# Main.net
KiCad netlist of a schematic drawn in Altium Designer
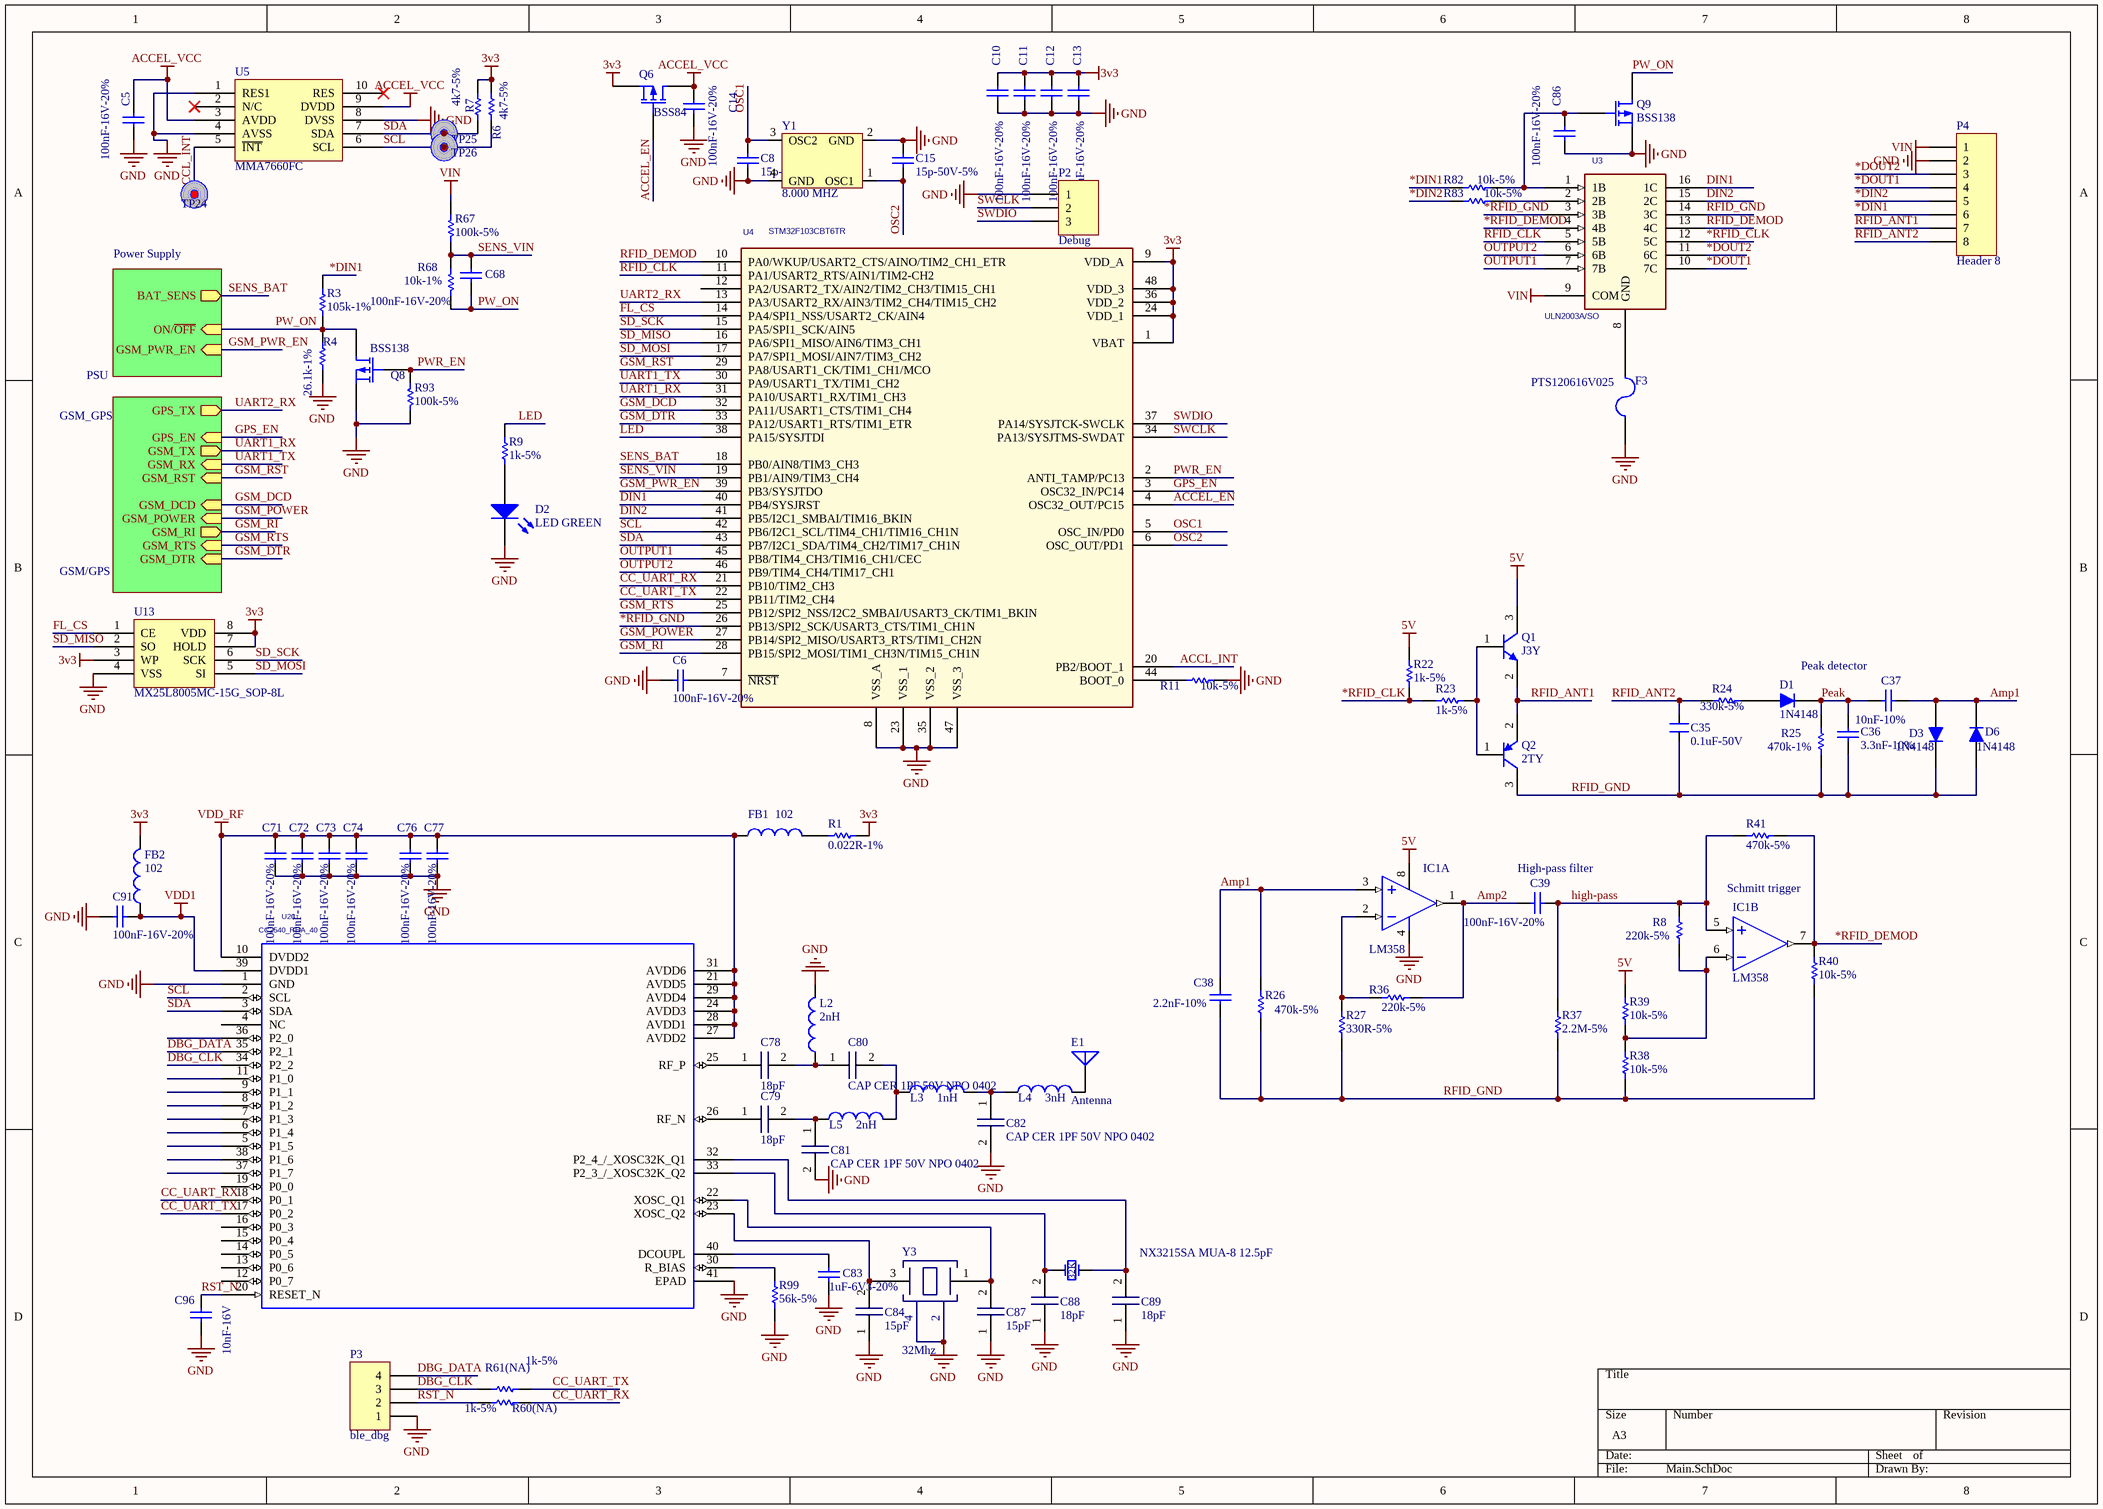
[diagram p0: Main.SchDoc]

(export (version "E")
  (design (tool "Eeschema 10.0.6"))
  (components
    (comp (ref "C5")
      (value "100nF-16V-20%")
      (footprint "C0402")
      (description "CAP CER 0.1UF 16V Y5V 0402")
      (fields
        (field (name "MANUFACTURER") "Yageo")
        (field (name "DIGI-KEY PART NUMBER") "311-1047-1-ND")
        (field (name "PUBLISHER") "Altium Limited")
      )
      (libsource (lib "Miscellaneous Devices") (part "Cap"))
    )
    (comp (ref "C6")
      (value "100nF-16V-20%")
      (footprint "C0402")
      (description "CAP CER 0.1UF 16V Y5V 0402")
      (fields
        (field (name "MANUFACTURER") "Yageo")
        (field (name "DIGI-KEY PART NUMBER") "311-1047-1-ND")
        (field (name "PUBLISHER") "Altium Limited")
      )
      (libsource (lib "Miscellaneous Devices") (part "Cap"))
    )
    (comp (ref "C8")
      (value "15p-50V-5%")
      (footprint "C0402")
      (description "CAP CER 15PF 50V 5% NPO 0402")
      (fields
        (field (name "MANUFACTURER") "Yageo")
        (field (name "DIGI-KEY PART NUMBER") "311-1017-1-ND")
        (field (name "PUBLISHER") "Altium Limited")
      )
      (libsource (lib "Miscellaneous Devices") (part "Cap"))
    )
    (comp (ref "C10")
      (value "100nF-16V-20%")
      (footprint "C0402")
      (description "CAP CER 0.1UF 16V Y5V 0402")
      (fields
        (field (name "MANUFACTURER") "Yageo")
        (field (name "DIGI-KEY PART NUMBER") "311-1047-1-ND")
        (field (name "PUBLISHER") "Altium Limited")
      )
      (libsource (lib "Miscellaneous Devices") (part "Cap"))
    )
    (comp (ref "C11")
      (value "100nF-16V-20%")
      (footprint "C0402")
      (description "CAP CER 0.1UF 16V Y5V 0402")
      (fields
        (field (name "MANUFACTURER") "Yageo")
        (field (name "DIGI-KEY PART NUMBER") "311-1047-1-ND")
        (field (name "PUBLISHER") "Altium Limited")
      )
      (libsource (lib "Miscellaneous Devices") (part "Cap"))
    )
    (comp (ref "C12")
      (value "100nF-16V-20%")
      (footprint "C0402")
      (description "CAP CER 0.1UF 16V Y5V 0402")
      (fields
        (field (name "MANUFACTURER") "Yageo")
        (field (name "DIGI-KEY PART NUMBER") "311-1047-1-ND")
        (field (name "PUBLISHER") "Altium Limited")
      )
      (libsource (lib "Miscellaneous Devices") (part "Cap"))
    )
    (comp (ref "C13")
      (value "100nF-16V-20%")
      (footprint "C0402")
      (description "CAP CER 0.1UF 16V Y5V 0402")
      (fields
        (field (name "MANUFACTURER") "Yageo")
        (field (name "DIGI-KEY PART NUMBER") "311-1047-1-ND")
        (field (name "PUBLISHER") "Altium Limited")
      )
      (libsource (lib "Miscellaneous Devices") (part "Cap"))
    )
    (comp (ref "C14")
      (value "100nF-16V-20%")
      (footprint "C0402")
      (description "CAP CER 0.1UF 16V Y5V 0402")
      (fields
        (field (name "MANUFACTURER") "Yageo")
        (field (name "DIGI-KEY PART NUMBER") "311-1047-1-ND")
        (field (name "PUBLISHER") "Altium Limited")
      )
      (libsource (lib "Miscellaneous Devices") (part "Cap"))
    )
    (comp (ref "C15")
      (value "15p-50V-5%")
      (footprint "C0402")
      (description "CAP CER 15PF 50V 5% NPO 0402")
      (fields
        (field (name "MANUFACTURER") "Yageo")
        (field (name "DIGI-KEY PART NUMBER") "311-1017-1-ND")
        (field (name "PUBLISHER") "Altium Limited")
      )
      (libsource (lib "Miscellaneous Devices") (part "Cap"))
    )
    (comp (ref "C35")
      (value "0.1uF-50V")
      (footprint "C0603")
      (description "CAP CER 0.1UF 50V Y5V 0603")
      (fields (field (name "DIGI-KEY PART NUMBER") "311-1343-2-ND") (field (name "MANUFACTURER") "Yageo"))
      (libsource (lib "syhaunguyen") (part "CN2"))
    )
    (comp (ref "C36")
      (value "3.3nF-10%")
      (footprint "C0402")
      (description "CAP CER 3300PF 50V 10% X7R 0402")
      (fields (field (name "DIGI-KEY PART NUMBER") "311-1034-2-ND") (field (name "MANUFACTURER") "Yageo"))
      (libsource (lib "Capacitor") (part "1nF-50V-C0805"))
    )
    (comp (ref "C37")
      (value "10nF-10%")
      (footprint "C0402")
      (description "Non-Polarized Capacitor")
      (fields (field (name "DIGI-KEY PART NUMBER") "CC0402KRX7R9BB103") (field (name "MANUFACTURER") "Yageo"))
      (libsource (lib "Capacitor") (part "10nF-50V-C0805"))
    )
    (comp (ref "C38")
      (value "2.2nF-10%")
      (footprint "C0402")
      (description "CAP CER 2200PF 50V 10% X7R 0402")
      (fields (field (name "DIGI-KEY PART NUMBER") "311-1037-2-ND") (field (name "MANUFACTURER") "Yageo"))
      (libsource (lib "Capacitor") (part "2.2nF-50V-C0805"))
    )
    (comp (ref "C39")
      (value "100nF-16V-20%")
      (footprint "C0402")
      (description "CAP CER 0.1UF 16V Y5V 0402")
      (fields
        (field (name "MANUFACTURER") "Yageo")
        (field (name "DIGI-KEY PART NUMBER") "311-1047-1-ND")
        (field (name "PUBLISHER") "Altium Limited")
      )
      (libsource (lib "Miscellaneous Devices") (part "Cap"))
    )
    (comp (ref "C68")
      (value "100nF-16V-20%")
      (footprint "C0402")
      (description "CAP CER 0.1UF 16V Y5V 0402")
      (fields
        (field (name "MANUFACTURER") "Yageo")
        (field (name "DIGI-KEY PART NUMBER") "311-1047-1-ND")
        (field (name "PUBLISHER") "Altium Limited")
      )
      (libsource (lib "Miscellaneous Devices") (part "Cap"))
    )
    (comp (ref "C71")
      (value "100nF-16V-20%")
      (footprint "C0402")
      (description "CAP CER 0.1UF 16V Y5V 0402")
      (fields
        (field (name "MANUFACTURER") "Yageo")
        (field (name "DIGI-KEY PART NUMBER") "311-1047-1-ND")
        (field (name "PUBLISHER") "Altium Limited")
      )
      (libsource (lib "Miscellaneous Devices") (part "Cap"))
    )
    (comp (ref "C72")
      (value "100nF-16V-20%")
      (footprint "C0402")
      (description "CAP CER 0.1UF 16V Y5V 0402")
      (fields
        (field (name "MANUFACTURER") "Yageo")
        (field (name "DIGI-KEY PART NUMBER") "311-1047-1-ND")
        (field (name "PUBLISHER") "Altium Limited")
      )
      (libsource (lib "Miscellaneous Devices") (part "Cap"))
    )
    (comp (ref "C73")
      (value "100nF-16V-20%")
      (footprint "C0402")
      (description "CAP CER 0.1UF 16V Y5V 0402")
      (fields
        (field (name "MANUFACTURER") "Yageo")
        (field (name "DIGI-KEY PART NUMBER") "311-1047-1-ND")
        (field (name "PUBLISHER") "Altium Limited")
      )
      (libsource (lib "Miscellaneous Devices") (part "Cap"))
    )
    (comp (ref "C74")
      (value "100nF-16V-20%")
      (footprint "C0402")
      (description "CAP CER 0.1UF 16V Y5V 0402")
      (fields
        (field (name "MANUFACTURER") "Yageo")
        (field (name "DIGI-KEY PART NUMBER") "311-1047-1-ND")
        (field (name "PUBLISHER") "Altium Limited")
      )
      (libsource (lib "Miscellaneous Devices") (part "Cap"))
    )
    (comp (ref "C76")
      (value "100nF-16V-20%")
      (footprint "C0402")
      (description "CAP CER 0.1UF 16V Y5V 0402")
      (fields
        (field (name "MANUFACTURER") "Yageo")
        (field (name "DIGI-KEY PART NUMBER") "311-1047-1-ND")
        (field (name "PUBLISHER") "Altium Limited")
      )
      (libsource (lib "Miscellaneous Devices") (part "Cap"))
    )
    (comp (ref "C77")
      (value "100nF-16V-20%")
      (footprint "C0402")
      (description "CAP CER 0.1UF 16V Y5V 0402")
      (fields
        (field (name "MANUFACTURER") "Yageo")
        (field (name "DIGI-KEY PART NUMBER") "311-1047-1-ND")
        (field (name "PUBLISHER") "Altium Limited")
      )
      (libsource (lib "Miscellaneous Devices") (part "Cap"))
    )
    (comp (ref "C78")
      (value "18pF")
      (footprint "C0402")
      (fields
        (field (name "MANUFACTURER") "Yageo")
        (field (name "DIGI-KEY PART NUMBER") "311-1018-1-ND")
        (field (name "MANUFACTURER PART NUMBER") "CC0402JRNPO9BN220")
      )
      (libsource (lib "Capacitor") (part "18pF"))
    )
    (comp (ref "C79")
      (value "18pF")
      (footprint "C0402")
      (fields
        (field (name "MANUFACTURER") "Yageo")
        (field (name "DIGI-KEY PART NUMBER") "311-1018-1-ND")
        (field (name "MANUFACTURER PART NUMBER") "CC0402JRNPO9BN220")
      )
      (libsource (lib "Capacitor") (part "18pF"))
    )
    (comp (ref "C80")
      (value "CAP CER 1PF 50V NPO 0402")
      (footprint "C0402")
      (fields
        (field (name "DIGI-KEY PART NUMBER") "CC0402CRNPO9BN1R0-ND")
        (field (name "MANUFACTURER") "Yageo")
        (field (name "MANUFACTURER PART NUMBER") "CC0402CRNPO9BN1R0")
      )
      (libsource (lib "Capacitor") (part "1pF"))
    )
    (comp (ref "C81")
      (value "CAP CER 1PF 50V NPO 0402")
      (footprint "C0402")
      (fields
        (field (name "DIGI-KEY PART NUMBER") "CC0402CRNPO9BN1R0-ND")
        (field (name "MANUFACTURER") "Yageo")
        (field (name "MANUFACTURER PART NUMBER") "CC0402CRNPO9BN1R0")
      )
      (libsource (lib "Capacitor") (part "1pF"))
    )
    (comp (ref "C82")
      (value "CAP CER 1PF 50V NPO 0402")
      (footprint "C0402")
      (fields
        (field (name "DIGI-KEY PART NUMBER") "CC0402CRNPO9BN1R0-ND")
        (field (name "MANUFACTURER") "Yageo")
        (field (name "MANUFACTURER PART NUMBER") "CC0402CRNPO9BN1R0")
      )
      (libsource (lib "Capacitor") (part "1pF"))
    )
    (comp (ref "C83")
      (value "1uF-6V3-20%")
      (footprint "C0402")
      (description "CAP CER 1UF 6.3V Y5V 0402")
      (fields
        (field (name "MANUFACTURER") "Yageo")
        (field (name "DIGI-KEY PART NUMBER") "311-1377-2-ND")
        (field (name "PUBLISHER") "Altium Limited")
      )
      (libsource (lib "Miscellaneous Devices") (part "Cap"))
    )
    (comp (ref "C84")
      (value "15pF")
      (footprint "C0402")
      (fields
        (field (name "MANUFACTURER") "Yageo")
        (field (name "DIGI-KEY PART NUMBER") "311-1018-1-ND")
        (field (name "MANUFACTURER PART NUMBER") "CC0402JRNPO9BN220")
      )
      (libsource (lib "Capacitor") (part "15pF"))
    )
    (comp (ref "C86")
      (value "100nF-16V-20%")
      (footprint "C0402")
      (description "CAP CER 0.1UF 16V Y5V 0402")
      (fields
        (field (name "MANUFACTURER") "Yageo")
        (field (name "DIGI-KEY PART NUMBER") "311-1047-1-ND")
        (field (name "PUBLISHER") "Altium Limited")
      )
      (libsource (lib "Miscellaneous Devices") (part "Cap"))
    )
    (comp (ref "C87")
      (value "15pF")
      (footprint "C0402")
      (fields
        (field (name "MANUFACTURER") "Yageo")
        (field (name "DIGI-KEY PART NUMBER") "311-1018-1-ND")
        (field (name "MANUFACTURER PART NUMBER") "CC0402JRNPO9BN220")
      )
      (libsource (lib "Capacitor") (part "15pF"))
    )
    (comp (ref "C88")
      (value "18pF")
      (footprint "C0402")
      (fields
        (field (name "MANUFACTURER") "Yageo")
        (field (name "DIGI-KEY PART NUMBER") "311-1018-1-ND")
        (field (name "MANUFACTURER PART NUMBER") "CC0402JRNPO9BN220")
      )
      (libsource (lib "Capacitor") (part "18pF"))
    )
    (comp (ref "C89")
      (value "18pF")
      (footprint "C0402")
      (fields
        (field (name "MANUFACTURER") "Yageo")
        (field (name "DIGI-KEY PART NUMBER") "311-1018-1-ND")
        (field (name "MANUFACTURER PART NUMBER") "CC0402JRNPO9BN220")
      )
      (libsource (lib "Capacitor") (part "18pF"))
    )
    (comp (ref "C91")
      (value "100nF-16V-20%")
      (footprint "C0402")
      (description "CAP CER 0.1UF 16V Y5V 0402")
      (fields
        (field (name "MANUFACTURER") "Yageo")
        (field (name "DIGI-KEY PART NUMBER") "311-1047-1-ND")
        (field (name "PUBLISHER") "Altium Limited")
      )
      (libsource (lib "Miscellaneous Devices") (part "Cap"))
    )
    (comp (ref "C96")
      (value "10nF-16V")
      (footprint "C0402")
      (description "CAP CER 10000PF 16V 10% X7R 0402")
      (fields (field (name "DIGI-KEY PART NUMBER") "311-1042-2-ND") (field (name "MANUFACTURER") "Yageo"))
      (libsource (lib "Capacitor_0402") (part "10nF-16V-C0402-10%"))
    )
    (comp (ref "D1")
      (value "1N4148")
      (footprint "DO-213AA")
      (description "DIODE SMALL SIG 100V 0.2A ALF2")
      (fields
        (field (name "DIGI-KEY PART NUMBER") "568-1360-1-ND")
        (field (name "MANUFACTURER") "NXP Semiconductors")
      )
      (libsource (lib "Active Components") (part "1N4148"))
    )
    (comp (ref "D2")
      (value "LED GREEN")
      (footprint "LED0603-G")
      (description "LED GREEN CLEAR THIN 0603 SMD")
      (fields
        (field (name "DIGI-KEY PART NUMBER") "160-1446-2-ND")
        (field (name "MANUFACTURER") "Lite-On Inc")
        (field (name "PUBLISHER") "Altium Limited")
      )
      (libsource (lib "Miscellaneous Devices") (part "LED2"))
    )
    (comp (ref "D3")
      (value "1N4148")
      (footprint "DO-213AA")
      (description "DIODE SMALL SIG 100V 0.2A ALF2")
      (fields
        (field (name "DIGI-KEY PART NUMBER") "568-1360-1-ND")
        (field (name "MANUFACTURER") "NXP Semiconductors")
      )
      (libsource (lib "Active Components") (part "1N4148"))
    )
    (comp (ref "D6")
      (value "1N4148")
      (footprint "DO-213AA")
      (description "DIODE SMALL SIG 100V 0.2A ALF2")
      (fields
        (field (name "DIGI-KEY PART NUMBER") "568-1360-1-ND")
        (field (name "MANUFACTURER") "NXP Semiconductors")
      )
      (libsource (lib "Active Components") (part "1N4148"))
    )
    (comp (ref "E1")
      (value "Antenna")
      (footprint "A10192-ANTENOVA")
      (description "Generic Antenna")
      (fields (field (name "PUBLISHER") "Altium Limited"))
      (libsource (lib "Miscellaneous Devices") (part "Antenna"))
    )
    (comp (ref "F3")
      (value "PTS120616V025")
      (footprint "PTC1206")
      (description "PTC RESETTABLE SMD 1206 16V .25A")
      (fields
        (field (name "DIGI-KEY PART NUMBER") "283-3137-2-ND")
        (field (name "MANUFACTURER") "Cooper Bussmann")
        (field (name "PUBLISHER") "Altium Limited")
      )
      (libsource (lib "Miscellaneous Devices") (part "Fuse 2"))
    )
    (comp (ref "FB1")
      (value "102")
      (footprint "R0402")
      (description "Inductor")
      (fields
        (field (name "DIGI-KEY PART NUMBER") "490-1174-1-ND")
        (field (name "MANUFACTURER PART NUMBER") "LQW18AN27NJ00D")
        (field (name "PUBLISHER") "Altium Limited")
      )
      (libsource (lib "Miscellaneous Devices") (part "Inductor"))
    )
    (comp (ref "FB2")
      (value "102")
      (footprint "R0402")
      (description "Inductor")
      (fields
        (field (name "DIGI-KEY PART NUMBER") "490-1174-1-ND")
        (field (name "MANUFACTURER PART NUMBER") "LQW18AN27NJ00D")
        (field (name "PUBLISHER") "Altium Limited")
      )
      (libsource (lib "Miscellaneous Devices") (part "Inductor"))
    )
    (comp (ref "IC1")
      (value "LM358")
      (footprint "soic8")
      (description "Low-Power Dual Operational Amplifier")
      (libsource (lib "IC") (part "LM358"))
    )
    (comp (ref "L2")
      (value "2nH")
      (footprint "R0402")
      (description "Inductor")
      (fields
        (field (name "DIGI-KEY PART NUMBER") "490-1174-1-ND")
        (field (name "MANUFACTURER PART NUMBER") "LQW18AN27NJ00D")
        (field (name "PUBLISHER") "Altium Limited")
      )
      (libsource (lib "Miscellaneous Devices") (part "Inductor"))
    )
    (comp (ref "L3")
      (value "1nH")
      (footprint "R0402")
      (description "Inductor")
      (fields
        (field (name "DIGI-KEY PART NUMBER") "490-1174-1-ND")
        (field (name "MANUFACTURER PART NUMBER") "LQW18AN27NJ00D")
        (field (name "PUBLISHER") "Altium Limited")
      )
      (libsource (lib "Miscellaneous Devices") (part "Inductor"))
    )
    (comp (ref "L4")
      (value "3nH")
      (footprint "R0402")
      (description "Inductor")
      (fields
        (field (name "DIGI-KEY PART NUMBER") "490-1174-1-ND")
        (field (name "MANUFACTURER PART NUMBER") "LQW18AN27NJ00D")
        (field (name "PUBLISHER") "Altium Limited")
      )
      (libsource (lib "Miscellaneous Devices") (part "Inductor"))
    )
    (comp (ref "L5")
      (value "2nH")
      (footprint "R0402")
      (description "Inductor")
      (fields
        (field (name "DIGI-KEY PART NUMBER") "490-1174-1-ND")
        (field (name "MANUFACTURER PART NUMBER") "LQW18AN27NJ00D")
        (field (name "PUBLISHER") "Altium Limited")
      )
      (libsource (lib "Miscellaneous Devices") (part "Inductor"))
    )
    (comp (ref "P2")
      (value "Debug")
      (footprint "HEADER_1.27mm_3PIN")
      (description "NA")
      (fields (field (name "PUBLISHER") "Altium Limited"))
      (libsource (lib "Miscellaneous Connectors") (part "Header 3"))
    )
    (comp (ref "P3")
      (value "ble_dbg")
      (footprint "HEADER_1.27mm_4PIN")
      (description "Header, 4-Pin")
      (fields (field (name "PUBLISHER") "Altium Limited"))
      (libsource (lib "Miscellaneous Connectors") (part "Header 4"))
    )
    (comp (ref "P4")
      (value "Header 8")
      (footprint "HDR1X8")
      (description "Header, 8-Pin")
      (fields (field (name "PUBLISHER") "Altium Limited"))
      (libsource (lib "Miscellaneous Connectors") (part "Header 8"))
    )
    (comp (ref "Q1")
      (value "J3Y")
      (footprint "SOT23_123")
      (description "NPN Bipolar Transistor")
      (libsource (lib "Active Components") (part "NPN_123"))
    )
    (comp (ref "Q2")
      (value "2TY")
      (footprint "SOT23_123")
      (description "PNP Bipolar Transistor")
      (libsource (lib "Active Components") (part "PNP_123"))
    )
    (comp (ref "Q6")
      (value "BSS84")
      (footprint "SOT23-3")
      (description "MOSFET P-CH 50V 130MA SOT23-3")
      (fields
        (field (name "DIGI-KEY PART NUMBER") "BSS84-FDITR-ND")
        (field (name "MANUFACTURER") "Diodes Inc")
        (field (name "PUBLISHER") "Altium Limited")
      )
      (libsource (lib "Miscellaneous Devices") (part "MOSFET-P"))
    )
    (comp (ref "Q8")
      (value "BSS138")
      (footprint "SOT23-3")
      (description "MOSFET N-CH 50V 200MA SOT23-3")
      (fields
        (field (name "DIGI-KEY PART NUMBER") "BSS138-FDICT-ND")
        (field (name "MANUFACTURER") "Diodes Inc")
        (field (name "PUBLISHER") "Altium Limited")
      )
      (libsource (lib "") (part "MOSFET-P_1"))
    )
    (comp (ref "Q9")
      (value "BSS138")
      (footprint "SOT23-3")
      (description "MOSFET N-CH 50V 200MA SOT23-3")
      (fields
        (field (name "DIGI-KEY PART NUMBER") "BSS138-FDICT-ND")
        (field (name "MANUFACTURER") "Diodes Inc")
        (field (name "PUBLISHER") "Altium Limited")
      )
      (libsource (lib "") (part "MOSFET-P_1"))
    )
    (comp (ref "R1")
      (value "0.022R-1%")
      (footprint "R0402")
      (description "RES 0.022 OHM 1/4W 1% 0805 SMD")
      (fields (field (name "DIGI-KEY PART NUMBER") "311-0.022NSTR-ND") (field (name "MANUFACTURER") "Yageo"))
      (libsource (lib "All_Resistor") (part "0.022R-1%-R0805"))
    )
    (comp (ref "R3")
      (value "105k-1%")
      (footprint "R0402")
      (description "RES 105k OHM 1/4W 1% 0805 SMD")
      (fields (field (name "DIGI-KEY PART NUMBER") "311-105KCRTR-ND") (field (name "MANUFACTURER") "Yageo"))
      (libsource (lib "All_Resistor") (part "105k-1%-R0805"))
    )
    (comp (ref "R4")
      (value "26.1k-1%")
      (footprint "R0402")
      (description "RES 26.1k OHM 1/4W 1% 0805 SMD")
      (fields (field (name "DIGI-KEY PART NUMBER") "311-26.1KCRTR-ND") (field (name "MANUFACTURER") "Yageo"))
      (libsource (lib "All_Resistor") (part "26.1k-1%-R0805"))
    )
    (comp (ref "R6")
      (value "4k7-5%")
      (footprint "R0402")
      (description "RES 4.7K OHM 1/16W 5% 0402 SMD")
      (fields
        (field (name "DIGI-KEY PART NUMBER") "311-4.7KJRCT-ND")
        (field (name "MANUFACTURER") "Yageo")
        (field (name "PUBLISHER") "Altium Limited")
      )
      (libsource (lib "Miscellaneous Devices") (part "Res1"))
    )
    (comp (ref "R7")
      (value "4k7-5%")
      (footprint "R0402")
      (description "RES 4.7K OHM 1/16W 5% 0402 SMD")
      (fields
        (field (name "DIGI-KEY PART NUMBER") "311-4.7KJRCT-ND")
        (field (name "MANUFACTURER") "Yageo")
        (field (name "PUBLISHER") "Altium Limited")
      )
      (libsource (lib "Miscellaneous Devices") (part "Res1"))
    )
    (comp (ref "R8")
      (value "220k-5%")
      (footprint "R0402")
      (description "RES 220k OHM 1/8W 5% 0805 SMD")
      (fields (field (name "DIGI-KEY PART NUMBER") "311-220KARTR-ND") (field (name "MANUFACTURER") "Yageo"))
      (libsource (lib "Resistor") (part "220k-5%-R0805"))
    )
    (comp (ref "R9")
      (value "1k-5%")
      (footprint "R0402")
      (description "RES 1.0K OHM 1/16W 5% 0402 SMD")
      (fields
        (field (name "DIGI-KEY PART NUMBER") "311-1.0KJRCT-ND")
        (field (name "MANUFACTURER") "Yageo")
        (field (name "PUBLISHER") "Altium Limited")
      )
      (libsource (lib "Miscellaneous Devices") (part "Res1"))
    )
    (comp (ref "R11")
      (value "10k-5%")
      (footprint "R0402")
      (description "RES 10K OHM 1/16W 5% 0402 SMD")
      (fields
        (field (name "DIGI-KEY PART NUMBER") "311-10KJRCT-ND")
        (field (name "MANUFACTURER") "Yageo")
        (field (name "PUBLISHER") "Altium Limited")
      )
      (libsource (lib "Miscellaneous Devices") (part "Res1"))
    )
    (comp (ref "R22")
      (value "1k-5%")
      (footprint "R0402")
      (description "RES 1k OHM 1/8W 5% 0805 SMD")
      (fields (field (name "DIGI-KEY PART NUMBER") "311-1.0KARTR-ND") (field (name "MANUFACTURER") "Yageo"))
      (libsource (lib "All_Resistor") (part "1k-5%-R0805"))
    )
    (comp (ref "R23")
      (value "1k-5%")
      (footprint "R0402")
      (description "RES 1k OHM 1/8W 5% 0805 SMD")
      (fields (field (name "DIGI-KEY PART NUMBER") "311-1.0KARTR-ND") (field (name "MANUFACTURER") "Yageo"))
      (libsource (lib "All_Resistor") (part "1k-5%-R0805"))
    )
    (comp (ref "R24")
      (value "330k-5%")
      (footprint "R0402")
      (description "RES 330k OHM 1/8W 5% 0805 SMD")
      (fields (field (name "DIGI-KEY PART NUMBER") "311-330KARTR-ND") (field (name "MANUFACTURER") "Yageo"))
      (libsource (lib "Resistor") (part "330k-5%-R0805"))
    )
    (comp (ref "R25")
      (value "470k-1%")
      (footprint "R0402")
      (description "RES 470k OHM 1/4W 1% 0805 SMD")
      (fields (field (name "DIGI-KEY PART NUMBER") "311-470KCRTR-ND") (field (name "MANUFACTURER") "Yageo"))
      (libsource (lib "Resistor") (part "470k-1%-R0805"))
    )
    (comp (ref "R26")
      (value "470k-5%")
      (footprint "R0402")
      (description "RES 470k OHM 1/8W 5% 0805 SMD")
      (fields (field (name "DIGI-KEY PART NUMBER") "311-470KARTR-ND") (field (name "MANUFACTURER") "Yageo"))
      (libsource (lib "Resistor") (part "470k-5%-R0805"))
    )
    (comp (ref "R27")
      (value "330R-5%")
      (footprint "R0402")
      (description "RES 330 OHM 1/8W 5% 0805 SMD")
      (fields (field (name "DIGI-KEY PART NUMBER") "311-330ARTR-ND") (field (name "MANUFACTURER") "Yageo"))
      (libsource (lib "Resistor") (part "330R-5%-R0805"))
    )
    (comp (ref "R36")
      (value "220k-5%")
      (footprint "R0402")
      (description "RES 220k OHM 1/8W 5% 0805 SMD")
      (fields (field (name "DIGI-KEY PART NUMBER") "311-220KARTR-ND") (field (name "MANUFACTURER") "Yageo"))
      (libsource (lib "Resistor") (part "220k-5%-R0805"))
    )
    (comp (ref "R37")
      (value "2.2M-5%")
      (footprint "R0402")
      (description "RES 2.2M OHM 1/8W 5% 0805 SMD")
      (fields (field (name "DIGI-KEY PART NUMBER") "311-2.2MARTR-ND") (field (name "MANUFACTURER") "Yageo"))
      (libsource (lib "Resistor") (part "2.2M-5%-R0805"))
    )
    (comp (ref "R38")
      (value "10k-5%")
      (footprint "R0402")
      (description "RES 10k OHM 1/8W 5% 0805 SMD")
      (fields (field (name "DIGI-KEY PART NUMBER") "311-10KARTR-ND") (field (name "MANUFACTURER") "Yageo"))
      (libsource (lib "Resistor") (part "10k-5%-R0805"))
    )
    (comp (ref "R39")
      (value "10k-5%")
      (footprint "R0402")
      (description "RES 10k OHM 1/8W 5% 0805 SMD")
      (fields (field (name "DIGI-KEY PART NUMBER") "311-10KARTR-ND") (field (name "MANUFACTURER") "Yageo"))
      (libsource (lib "Resistor") (part "10k-5%-R0805"))
    )
    (comp (ref "R40")
      (value "10k-5%")
      (footprint "R0402")
      (description "RES 10k OHM 1/8W 5% 0805 SMD")
      (fields (field (name "DIGI-KEY PART NUMBER") "311-10KARTR-ND") (field (name "MANUFACTURER") "Yageo"))
      (libsource (lib "Resistor") (part "10k-5%-R0805"))
    )
    (comp (ref "R41")
      (value "470k-5%")
      (footprint "R0402")
      (description "RES 470k OHM 1/8W 5% 0805 SMD")
      (fields (field (name "DIGI-KEY PART NUMBER") "311-470KARTR-ND") (field (name "MANUFACTURER") "Yageo"))
      (libsource (lib "Resistor") (part "470k-5%-R0805"))
    )
    (comp (ref "R60(NA)")
      (value "1k-5%")
      (footprint "R0402")
      (description "RES 1.0K OHM 1/16W 5% 0402 SMD")
      (fields
        (field (name "DIGI-KEY PART NUMBER") "311-1.0KJRCT-ND")
        (field (name "MANUFACTURER") "Yageo")
        (field (name "PUBLISHER") "Altium Limited")
      )
      (libsource (lib "Miscellaneous Devices") (part "Res1"))
    )
    (comp (ref "R61(NA)")
      (value "1k-5%")
      (footprint "R0402")
      (description "RES 1.0K OHM 1/16W 5% 0402 SMD")
      (fields
        (field (name "DIGI-KEY PART NUMBER") "311-1.0KJRCT-ND")
        (field (name "MANUFACTURER") "Yageo")
        (field (name "PUBLISHER") "Altium Limited")
      )
      (libsource (lib "Miscellaneous Devices") (part "Res1"))
    )
    (comp (ref "R67")
      (value "100k-5%")
      (footprint "R0402")
      (description "RES 100K OHM 1/16W 5% 0402 SMD")
      (fields
        (field (name "DIGI-KEY PART NUMBER") "311-100KJRCT-ND")
        (field (name "MANUFACTURER") "Yageo")
        (field (name "PUBLISHER") "Altium Limited")
      )
      (libsource (lib "Miscellaneous Devices") (part "Res1"))
    )
    (comp (ref "R68")
      (value "10k-1%")
      (footprint "R0402")
      (description "RES 10.0K OHM 1/16W 1% 0402 SMD")
      (fields
        (field (name "DIGI-KEY PART NUMBER") "311-10.0KLRTR-ND")
        (field (name "MANUFACTURER") "Yageo")
        (field (name "PUBLISHER") "Altium Limited")
      )
      (libsource (lib "Miscellaneous Devices") (part "Res1"))
    )
    (comp (ref "R82")
      (value "10k-5%")
      (footprint "R0402")
      (description "RES 10K OHM 1/16W 5% 0402 SMD")
      (fields
        (field (name "DIGI-KEY PART NUMBER") "311-10KJRCT-ND")
        (field (name "MANUFACTURER") "Yageo")
        (field (name "PUBLISHER") "Altium Limited")
      )
      (libsource (lib "Miscellaneous Devices") (part "Res1"))
    )
    (comp (ref "R83")
      (value "10k-5%")
      (footprint "R0402")
      (description "RES 10K OHM 1/16W 5% 0402 SMD")
      (fields
        (field (name "DIGI-KEY PART NUMBER") "311-10KJRCT-ND")
        (field (name "MANUFACTURER") "Yageo")
        (field (name "PUBLISHER") "Altium Limited")
      )
      (libsource (lib "Miscellaneous Devices") (part "Res1"))
    )
    (comp (ref "R93")
      (value "100k-5%")
      (footprint "R0402")
      (description "RES 100K OHM 1/16W 5% 0402 SMD")
      (fields
        (field (name "DIGI-KEY PART NUMBER") "311-100KJRCT-ND")
        (field (name "MANUFACTURER") "Yageo")
        (field (name "PUBLISHER") "Altium Limited")
      )
      (libsource (lib "Miscellaneous Devices") (part "Res1"))
    )
    (comp (ref "R99")
      (value "56k-5%")
      (footprint "R0402")
      (description "RES 56k OHM 1/8W 5% 0805 SMD")
      (fields (field (name "DIGI-KEY PART NUMBER") "311-56KARTR-ND") (field (name "MANUFACTURER") "Yageo"))
      (libsource (lib "All_Resistor") (part "56k-5%-R0805"))
    )
    (comp (ref "TP24") (value "TP") (footprint "test_point") (libsource (lib "Lib") (part "TP")))
    (comp (ref "TP25") (value "TP") (footprint "test_point") (libsource (lib "Lib") (part "TP")))
    (comp (ref "TP26") (value "TP") (footprint "test_point") (libsource (lib "Lib") (part "TP")))
    (comp (ref "U3")
      (value "ULN2003A/SO")
      (footprint "SO16-150mil")
      (description "IC DARL TRANS ARRAY 16-SOIC")
      (fields
        (field (name "DIGI-KEY PART NUMBER") "296-1368-2-ND")
        (field (name "MANUFACTURER PART NUMBER") "ULN2003ADR")
      )
      (libsource (lib "*") (part "ULN2003A/SO_0"))
    )
    (comp (ref "U4")
      (value "STM32F103CBT6TR")
      (footprint "TQFP-48-P0.5")
      (description "MCU ARM 128K FLASH/TIMER")
      (fields
        (field (name "DIGI-KEY PART NUMBER") "497-6288-ND")
        (field (name "MANUFACTURER") "STMicroelectronics")
      )
      (libsource (lib "*") (part "ATmega128_4"))
    )
    (comp (ref "U5")
      (value "MMA7660FC")
      (footprint "MMA7660FC")
      (description "ACCELEROMETER 3X3 DGTL 10-DFN")
      (fields
        (field (name "DIGI-KEY PART NUMBER") "MMA7660FCT-ND")
        (field (name "MANUFACTURER") "Freescale Semiconductor")
      )
      (libsource (lib "Lib") (part "MMA7660FC"))
    )
    (comp (ref "U13")
      (value "MX25L8005MC-15G_SOP-8L")
      (footprint "SO8-200mil")
      (fields (field (name "MANUFACTURER") "Tyrone"))
      (libsource (lib "My LB") (part "FlashIC"))
    )
    (comp (ref "U20")
      (value "CC2540_RHA_40")
      (footprint "CC254x")
      (description "2.4GHz Bluetooth Low Energy System-on-Chip Solution")
      (fields (field (name "MANUFACTURER") "Texas Instruments") (field (name "GENERIC_PART_NUMBER") "CC2540"))
      (libsource (lib "2013-05-06_12-03-49") (part "CC2540_RHA_40"))
    )
    (comp (ref "Y1")
      (value "8.000 MHZ")
      (footprint "SMD CRYSTAL 4 x 2.5")
      (description "CRYSTAL 8.000 MHZ 18PF SMD")
      (fields
        (field (name "DIGI-KEY PART NUMBER") "887-1452-2-ND")
        (field (name "MANUFACTURER") "TXC CORPORATION")
      )
      (libsource (lib "Schlib1") (part "CRYSTAL-SMT"))
    )
    (comp (ref "Y3")
      (value "32Mhz")
      (footprint "SMD CRYSTAL 2.5 x 2")
      (libsource (lib "msp430g2553") (part "XTAL"))
    )
    (comp (ref "Y4")
      (value "NX3215SA MUA-8 12.5pF")
      (footprint "Crystal-3.2x1.5")
      (description "Crystal Oscillator")
      (fields (field (name "PUBLISHER") "Altium Limited"))
      (libsource (lib "Schematic") (part "XTAL/32KHz"))
    )
  )
  (nets
    (net (code "1") (name "/*DIN1") (class "Default")
      (node (ref "P4") (pin "6") (pinfunction "6_6") (pintype "passive"))
      (node (ref "R3") (pin "2") (pinfunction "2_2") (pintype "passive"))
      (node (ref "R82") (pin "1") (pinfunction "1_1") (pintype "passive"))
    )
    (net (code "2") (name "/*DIN2") (class "Default")
      (node (ref "P4") (pin "5") (pinfunction "5_5") (pintype "passive"))
      (node (ref "R83") (pin "2") (pinfunction "2_2") (pintype "passive"))
    )
    (net (code "3") (name "/*DOUT1") (class "Default")
      (node (ref "P4") (pin "4") (pinfunction "4_4") (pintype "passive"))
      (node (ref "U3") (pin "10") (pinfunction "7C_10") (pintype "open_collector"))
    )
    (net (code "4") (name "/*DOUT2") (class "Default")
      (node (ref "P4") (pin "3") (pinfunction "3_3") (pintype "passive"))
      (node (ref "U3") (pin "11") (pinfunction "6C_11") (pintype "open_collector"))
    )
    (net (code "5") (name "/*RFID_CLK") (class "Default")
      (node (ref "R22") (pin "1") (pinfunction "1_1") (pintype "passive"))
      (node (ref "R23") (pin "2") (pinfunction "2_2") (pintype "passive"))
      (node (ref "U3") (pin "12") (pinfunction "5C_12") (pintype "open_collector"))
    )
    (net (code "6") (name "/*RFID_DEMOD") (class "Default")
      (node (ref "IC1") (pin "7") (pinfunction "OUT_7") (pintype "output"))
      (node (ref "R40") (pin "2") (pinfunction "2_2") (pintype "passive"))
      (node (ref "R41") (pin "1") (pinfunction "1_1") (pintype "passive"))
      (node (ref "U3") (pin "4") (pinfunction "4B_4") (pintype "input"))
    )
    (net (code "7") (name "/*RFID_GND") (class "Default")
      (node (ref "U3") (pin "3") (pinfunction "3B_3") (pintype "input"))
      (node (ref "U4") (pin "26") (pinfunction "PB13/SPI2_SCK/USART3_CTS/TIM1_CH1N_26") (pintype "passive"))
    )
    (net (code "8") (name "/ACCEL_EN") (class "Default")
      (node (ref "Q6") (pin "1") (pinfunction "G_1") (pintype "passive"))
      (node (ref "U4") (pin "4") (pinfunction "OSC32_OUT/PC15_4") (pintype "passive"))
    )
    (net (code "9") (name "/ACCL_INT") (class "Default")
      (node (ref "TP24") (pin "1") (pinfunction "TP_1") (pintype "passive"))
      (node (ref "U4") (pin "20") (pinfunction "PB2/BOOT_1_20") (pintype "passive"))
      (node (ref "U5") (pin "5") (pinfunction "~{INT}_5") (pintype "passive"))
    )
    (net (code "10") (name "/Amp1") (class "Default")
      (node (ref "C37") (pin "2") (pinfunction "2_2") (pintype "passive"))
      (node (ref "C38") (pin "2") (pinfunction "2_2") (pintype "passive"))
      (node (ref "D3") (pin "1") (pinfunction "A_1") (pintype "passive"))
      (node (ref "D6") (pin "2") (pinfunction "K_2") (pintype "passive"))
      (node (ref "IC1") (pin "3") (pinfunction "IN+_3") (pintype "input"))
      (node (ref "R26") (pin "1") (pinfunction "1_1") (pintype "passive"))
    )
    (net (code "11") (name "/Amp2") (class "Default")
      (node (ref "C39") (pin "2") (pinfunction "2_2") (pintype "passive"))
      (node (ref "IC1") (pin "1") (pinfunction "OUT_1") (pintype "output"))
      (node (ref "R36") (pin "1") (pinfunction "1_1") (pintype "passive"))
    )
    (net (code "12") (name "/CC_UART_RX") (class "Default")
      (node (ref "R60(NA)") (pin "1") (pinfunction "1_1") (pintype "passive"))
      (node (ref "U20") (pin "18") (pinfunction "P0_1_18") (pintype "bidirectional"))
      (node (ref "U4") (pin "21") (pinfunction "PB10/TIM2_CH3_21") (pintype "passive"))
    )
    (net (code "13") (name "/CC_UART_TX") (class "Default")
      (node (ref "R61(NA)") (pin "1") (pinfunction "1_1") (pintype "passive"))
      (node (ref "U20") (pin "17") (pinfunction "P0_2_17") (pintype "bidirectional"))
      (node (ref "U4") (pin "22") (pinfunction "PB11/TIM2_CH4_22") (pintype "passive"))
    )
    (net (code "14") (name "/DBG_CLK") (class "Default")
      (node (ref "P3") (pin "3") (pinfunction "3_3") (pintype "passive"))
      (node (ref "R61(NA)") (pin "2") (pinfunction "2_2") (pintype "passive"))
      (node (ref "U20") (pin "34") (pinfunction "P2_2_34") (pintype "bidirectional"))
    )
    (net (code "15") (name "/DBG_DATA") (class "Default")
      (node (ref "P3") (pin "4") (pinfunction "4_4") (pintype "passive"))
      (node (ref "U20") (pin "35") (pinfunction "P2_1_35") (pintype "bidirectional"))
    )
    (net (code "16") (name "/DIN1") (class "Default")
      (node (ref "U3") (pin "16") (pinfunction "1C_16") (pintype "open_collector"))
      (node (ref "U4") (pin "40") (pinfunction "PB4/SYSJRST_40") (pintype "passive"))
    )
    (net (code "17") (name "/DIN2") (class "Default")
      (node (ref "U3") (pin "15") (pinfunction "2C_15") (pintype "open_collector"))
      (node (ref "U4") (pin "41") (pinfunction "PB5/I2C1_SMBAI/TIM16_BKIN_41") (pintype "passive"))
    )
    (net (code "18") (name "/FL_CS") (class "Default")
      (node (ref "U13") (pin "1") (pinfunction "CE_1") (pintype "passive"))
      (node (ref "U4") (pin "14") (pinfunction "PA4/SPI1_NSS/USART2_CK/AIN4_14") (pintype "passive"))
    )
    (net (code "19") (name "/GPS_EN") (class "Default")
      (node (ref "U4") (pin "3") (pinfunction "OSC32_IN/PC14_3") (pintype "passive"))
    )
    (net (code "20") (name "/GSM_DCD") (class "Default")
      (node (ref "U4") (pin "32") (pinfunction "PA11/USART1_CTS/TIM1_CH4_32") (pintype "passive"))
    )
    (net (code "21") (name "/GSM_DTR") (class "Default")
      (node (ref "U4") (pin "33") (pinfunction "PA12/USART1_RTS/TIM1_ETR_33") (pintype "passive"))
    )
    (net (code "22") (name "/GSM_POWER") (class "Default")
      (node (ref "U4") (pin "27") (pinfunction "PB14/SPI2_MISO/USART3_RTS/TIM1_CH2N_27") (pintype "passive"))
    )
    (net (code "23") (name "/GSM_PWR_EN") (class "Default")
      (node (ref "U4") (pin "39") (pinfunction "PB3/SYSJTDO_39") (pintype "passive"))
    )
    (net (code "24") (name "/GSM_RI") (class "Default")
      (node (ref "U4") (pin "28") (pinfunction "PB15/SPI2_MOSI/TIM1_CH3N/TIM15_CH1N_28") (pintype "passive"))
    )
    (net (code "25") (name "/GSM_RST") (class "Default")
      (node (ref "U4") (pin "29") (pinfunction "PA8/USART1_CK/TIM1_CH1/MCO_29") (pintype "passive"))
    )
    (net (code "26") (name "/GSM_RTS") (class "Default")
      (node (ref "U4") (pin "25") (pinfunction "PB12/SPI2_NSS/I2C2_SMBAI/USART3_CK/TIM1_BKIN_25") (pintype "passive"))
    )
    (net (code "27") (name "/LED") (class "Default")
      (node (ref "R9") (pin "2") (pinfunction "2_2") (pintype "passive"))
      (node (ref "U4") (pin "38") (pinfunction "PA15/SYSJTDI_38") (pintype "passive"))
    )
    (net (code "28") (name "/OSC1") (class "Default")
      (node (ref "C8") (pin "2") (pinfunction "2_2") (pintype "passive"))
      (node (ref "U4") (pin "5") (pinfunction "OSC_IN/PD0_5") (pintype "passive"))
      (node (ref "Y1") (pin "3") (pinfunction "OSC2_3") (pintype "passive"))
    )
    (net (code "29") (name "/OSC2") (class "Default")
      (node (ref "C15") (pin "1") (pinfunction "1_1") (pintype "passive"))
      (node (ref "U4") (pin "6") (pinfunction "OSC_OUT/PD1_6") (pintype "passive"))
      (node (ref "Y1") (pin "1") (pinfunction "OSC1_1") (pintype "passive"))
    )
    (net (code "30") (name "/OUTPUT1") (class "Default")
      (node (ref "U3") (pin "7") (pinfunction "7B_7") (pintype "input"))
      (node (ref "U4") (pin "45") (pinfunction "PB8/TIM4_CH3/TIM16_CH1/CEC_45") (pintype "passive"))
    )
    (net (code "31") (name "/OUTPUT2") (class "Default")
      (node (ref "U3") (pin "6") (pinfunction "6B_6") (pintype "input"))
      (node (ref "U4") (pin "46") (pinfunction "PB9/TIM4_CH4/TIM17_CH1_46") (pintype "passive"))
    )
    (net (code "32") (name "/PWR_EN") (class "Default")
      (node (ref "Q8") (pin "1") (pinfunction "G_1") (pintype "passive"))
      (node (ref "R93") (pin "1") (pinfunction "1_1") (pintype "passive"))
      (node (ref "U4") (pin "2") (pinfunction "ANTI_TAMP/PC13_2") (pintype "passive"))
    )
    (net (code "33") (name "/PW_ON") (class "Default")
      (node (ref "C68") (pin "1") (pinfunction "1_1") (pintype "passive"))
      (node (ref "Q8") (pin "3") (pinfunction "D_3") (pintype "passive"))
      (node (ref "Q9") (pin "3") (pinfunction "D_3") (pintype "passive"))
      (node (ref "R3") (pin "1") (pinfunction "1_1") (pintype "passive"))
      (node (ref "R4") (pin "2") (pinfunction "2_2") (pintype "passive"))
      (node (ref "R68") (pin "1") (pinfunction "1_1") (pintype "passive"))
    )
    (net (code "34") (name "/Peak") (class "Default")
      (node (ref "C36") (pin "1") (pinfunction "1_1") (pintype "passive"))
      (node (ref "C37") (pin "1") (pinfunction "1_1") (pintype "passive"))
      (node (ref "D1") (pin "2") (pinfunction "K_2") (pintype "passive"))
      (node (ref "R25") (pin "1") (pinfunction "1_1") (pintype "passive"))
    )
    (net (code "35") (name "/RFID_ANT1") (class "Default")
      (node (ref "P4") (pin "7") (pinfunction "7_7") (pintype "passive"))
      (node (ref "Q1") (pin "2") (pinfunction "E_2") (pintype "passive"))
      (node (ref "Q2") (pin "2") (pinfunction "E_2") (pintype "passive"))
    )
    (net (code "36") (name "/RFID_ANT2") (class "Default")
      (node (ref "C35") (pin "2") (pinfunction "2_2") (pintype "passive"))
      (node (ref "P4") (pin "8") (pinfunction "8_8") (pintype "passive"))
      (node (ref "R24") (pin "2") (pinfunction "2_2") (pintype "passive"))
    )
    (net (code "37") (name "/RFID_CLK") (class "Default")
      (node (ref "U3") (pin "5") (pinfunction "5B_5") (pintype "input"))
      (node (ref "U4") (pin "11") (pinfunction "PA1/USART2_RTS/AIN1/TIM2-CH2_11") (pintype "passive"))
    )
    (net (code "38") (name "/RFID_DEMOD") (class "Default")
      (node (ref "U3") (pin "13") (pinfunction "4C_13") (pintype "open_collector"))
      (node (ref "U4") (pin "10") (pinfunction "PA0/WKUP/USART2_CTS/AINO/TIM2_CH1_ETR_10") (pintype "passive"))
    )
    (net (code "39") (name "/RFID_GND") (class "Default")
      (node (ref "C35") (pin "1") (pinfunction "1_1") (pintype "passive"))
      (node (ref "C36") (pin "2") (pinfunction "2_2") (pintype "passive"))
      (node (ref "C38") (pin "1") (pinfunction "1_1") (pintype "passive"))
      (node (ref "D3") (pin "2") (pinfunction "K_2") (pintype "passive"))
      (node (ref "D6") (pin "1") (pinfunction "A_1") (pintype "passive"))
      (node (ref "Q2") (pin "3") (pinfunction "C_3") (pintype "passive"))
      (node (ref "R25") (pin "2") (pinfunction "2_2") (pintype "passive"))
      (node (ref "R26") (pin "2") (pinfunction "2_2") (pintype "passive"))
      (node (ref "R27") (pin "1") (pinfunction "1_1") (pintype "passive"))
      (node (ref "R37") (pin "1") (pinfunction "1_1") (pintype "passive"))
      (node (ref "R38") (pin "2") (pinfunction "2_2") (pintype "passive"))
      (node (ref "R40") (pin "1") (pinfunction "1_1") (pintype "passive"))
      (node (ref "U3") (pin "14") (pinfunction "3C_14") (pintype "open_collector"))
    )
    (net (code "40") (name "/RST_N") (class "Default")
      (node (ref "C96") (pin "2") (pinfunction "2_2") (pintype "passive"))
      (node (ref "P3") (pin "2") (pinfunction "2_2") (pintype "passive"))
      (node (ref "R60(NA)") (pin "2") (pinfunction "2_2") (pintype "passive"))
      (node (ref "U20") (pin "20") (pinfunction "RESET_N_20") (pintype "input"))
    )
    (net (code "41") (name "/SCL") (class "Default")
      (node (ref "R6") (pin "1") (pinfunction "1_1") (pintype "passive"))
      (node (ref "TP26") (pin "1") (pinfunction "TP_1") (pintype "passive"))
      (node (ref "U20") (pin "2") (pinfunction "SCL_2") (pintype "bidirectional"))
      (node (ref "U4") (pin "42") (pinfunction "PB6/I2C1_SCL/TIM4_CH1/TIM16_CH1N_42") (pintype "passive"))
      (node (ref "U5") (pin "6") (pinfunction "SCL_6") (pintype "passive"))
    )
    (net (code "42") (name "/SDA") (class "Default")
      (node (ref "R7") (pin "1") (pinfunction "1_1") (pintype "passive"))
      (node (ref "TP25") (pin "1") (pinfunction "TP_1") (pintype "passive"))
      (node (ref "U20") (pin "3") (pinfunction "SDA_3") (pintype "bidirectional"))
      (node (ref "U4") (pin "43") (pinfunction "PB7/I2C1_SDA/TIM4_CH2/TIM17_CH1N_43") (pintype "passive"))
      (node (ref "U5") (pin "7") (pinfunction "SDA_7") (pintype "passive"))
    )
    (net (code "43") (name "/SD_MISO") (class "Default")
      (node (ref "U13") (pin "2") (pinfunction "SO_2") (pintype "passive"))
      (node (ref "U4") (pin "16") (pinfunction "PA6/SPI1_MISO/AIN6/TIM3_CH1_16") (pintype "passive"))
    )
    (net (code "44") (name "/SD_MOSI") (class "Default")
      (node (ref "U13") (pin "5") (pinfunction "SI_5") (pintype "passive"))
      (node (ref "U4") (pin "17") (pinfunction "PA7/SPI1_MOSI/AIN7/TIM3_CH2_17") (pintype "passive"))
    )
    (net (code "45") (name "/SD_SCK") (class "Default")
      (node (ref "U13") (pin "6") (pinfunction "SCK_6") (pintype "passive"))
      (node (ref "U4") (pin "15") (pinfunction "PA5/SPI1_SCK/AIN5_15") (pintype "passive"))
    )
    (net (code "46") (name "/SENS_BAT") (class "Default")
      (node (ref "U4") (pin "18") (pinfunction "PB0/AIN8/TIM3_CH3_18") (pintype "passive"))
    )
    (net (code "47") (name "/SENS_VIN") (class "Default")
      (node (ref "C68") (pin "2") (pinfunction "2_2") (pintype "passive"))
      (node (ref "R67") (pin "2") (pinfunction "2_2") (pintype "passive"))
      (node (ref "R68") (pin "2") (pinfunction "2_2") (pintype "passive"))
      (node (ref "U4") (pin "19") (pinfunction "PB1/AIN9/TIM3_CH4_19") (pintype "passive"))
    )
    (net (code "48") (name "/SWCLK") (class "Default")
      (node (ref "P2") (pin "2") (pinfunction "2_2") (pintype "passive"))
      (node (ref "U4") (pin "34") (pinfunction "PA13/SYSJTMS-SWDAT_34") (pintype "passive"))
    )
    (net (code "49") (name "/SWDIO") (class "Default")
      (node (ref "P2") (pin "3") (pinfunction "3_3") (pintype "passive"))
      (node (ref "U4") (pin "37") (pinfunction "PA14/SYSJTCK-SWCLK_37") (pintype "passive"))
    )
    (net (code "50") (name "/UART1_RX") (class "Default")
      (node (ref "U4") (pin "31") (pinfunction "PA10/USART1_RX/TIM1_CH3_31") (pintype "passive"))
    )
    (net (code "51") (name "/UART1_TX") (class "Default")
      (node (ref "U4") (pin "30") (pinfunction "PA9/USART1_TX/TIM1_CH2_30") (pintype "passive"))
    )
    (net (code "52") (name "/UART2_RX") (class "Default")
      (node (ref "U4") (pin "13") (pinfunction "PA3/USART2_RX/AIN3/TIM2_CH4/TIM15_CH2_13") (pintype "passive"))
    )
    (net (code "53") (name "/high-pass") (class "Default")
      (node (ref "C39") (pin "1") (pinfunction "1_1") (pintype "passive"))
      (node (ref "IC1") (pin "5") (pinfunction "IN+_5") (pintype "input"))
      (node (ref "R37") (pin "2") (pinfunction "2_2") (pintype "passive"))
      (node (ref "R41") (pin "2") (pinfunction "2_2") (pintype "passive"))
      (node (ref "R8") (pin "2") (pinfunction "2_2") (pintype "passive"))
    )
    (net (code "54") (name "3v3") (class "Default")
      (node (ref "C10") (pin "1") (pinfunction "1_1") (pintype "passive"))
      (node (ref "C11") (pin "1") (pinfunction "1_1") (pintype "passive"))
      (node (ref "C12") (pin "1") (pinfunction "1_1") (pintype "passive"))
      (node (ref "C13") (pin "1") (pinfunction "1_1") (pintype "passive"))
      (node (ref "FB2") (pin "2") (pinfunction "2_2") (pintype "passive"))
      (node (ref "Q6") (pin "2") (pinfunction "S_2") (pintype "passive"))
      (node (ref "R1") (pin "2") (pinfunction "2_2") (pintype "passive"))
      (node (ref "R6") (pin "2") (pinfunction "2_2") (pintype "passive"))
      (node (ref "R7") (pin "2") (pinfunction "2_2") (pintype "passive"))
      (node (ref "U13") (pin "3") (pinfunction "WP_3") (pintype "passive"))
      (node (ref "U13") (pin "7") (pinfunction "HOLD_7") (pintype "passive"))
      (node (ref "U13") (pin "8") (pinfunction "VDD_8") (pintype "passive"))
      (node (ref "U4") (pin "1") (pinfunction "VBAT_1") (pintype "passive"))
      (node (ref "U4") (pin "24") (pinfunction "VDD_1_24") (pintype "passive"))
      (node (ref "U4") (pin "36") (pinfunction "VDD_2_36") (pintype "passive"))
      (node (ref "U4") (pin "48") (pinfunction "VDD_3_48") (pintype "passive"))
      (node (ref "U4") (pin "9") (pinfunction "VDD_A_9") (pintype "passive"))
    )
    (net (code "55") (name "5V") (class "Default")
      (node (ref "IC1") (pin "8") (pinfunction "+V_8") (pintype "passive"))
      (node (ref "Q1") (pin "3") (pinfunction "C_3") (pintype "passive"))
      (node (ref "R22") (pin "2") (pinfunction "2_2") (pintype "passive"))
      (node (ref "R39") (pin "1") (pinfunction "1_1") (pintype "passive"))
    )
    (net (code "56") (name "ACCEL_VCC") (class "Default")
      (node (ref "C14") (pin "2") (pinfunction "2_2") (pintype "passive"))
      (node (ref "C5") (pin "2") (pinfunction "2_2") (pintype "passive"))
      (node (ref "Q6") (pin "3") (pinfunction "D_3") (pintype "passive"))
      (node (ref "U5") (pin "3") (pinfunction "AVDD_3") (pintype "passive"))
      (node (ref "U5") (pin "9") (pinfunction "DVDD_9") (pintype "passive"))
    )
    (net (code "57") (name "GND") (class "Default")
      (node (ref "C10") (pin "2") (pinfunction "2_2") (pintype "passive"))
      (node (ref "C11") (pin "2") (pinfunction "2_2") (pintype "passive"))
      (node (ref "C12") (pin "2") (pinfunction "2_2") (pintype "passive"))
      (node (ref "C13") (pin "2") (pinfunction "2_2") (pintype "passive"))
      (node (ref "C14") (pin "1") (pinfunction "1_1") (pintype "passive"))
      (node (ref "C15") (pin "2") (pinfunction "2_2") (pintype "passive"))
      (node (ref "C5") (pin "1") (pinfunction "1_1") (pintype "passive"))
      (node (ref "C6") (pin "2") (pinfunction "2_2") (pintype "passive"))
      (node (ref "C71") (pin "2") (pinfunction "2_2") (pintype "passive"))
      (node (ref "C72") (pin "2") (pinfunction "2_2") (pintype "passive"))
      (node (ref "C73") (pin "2") (pinfunction "2_2") (pintype "passive"))
      (node (ref "C74") (pin "2") (pinfunction "2_2") (pintype "passive"))
      (node (ref "C76") (pin "2") (pinfunction "2_2") (pintype "passive"))
      (node (ref "C77") (pin "2") (pinfunction "2_2") (pintype "passive"))
      (node (ref "C8") (pin "1") (pinfunction "1_1") (pintype "passive"))
      (node (ref "C81") (pin "2") (pinfunction "2_2") (pintype "passive"))
      (node (ref "C82") (pin "2") (pinfunction "2_2") (pintype "passive"))
      (node (ref "C83") (pin "2") (pinfunction "2_2") (pintype "passive"))
      (node (ref "C84") (pin "1") (pinfunction "1_1") (pintype "passive"))
      (node (ref "C86") (pin "1") (pinfunction "1_1") (pintype "passive"))
      (node (ref "C87") (pin "1") (pinfunction "1_1") (pintype "passive"))
      (node (ref "C88") (pin "1") (pinfunction "1_1") (pintype "passive"))
      (node (ref "C89") (pin "1") (pinfunction "1_1") (pintype "passive"))
      (node (ref "C91") (pin "1") (pinfunction "1_1") (pintype "passive"))
      (node (ref "C96") (pin "1") (pinfunction "1_1") (pintype "passive"))
      (node (ref "D2") (pin "2") (pinfunction "K_2") (pintype "passive"))
      (node (ref "F3") (pin "2") (pinfunction "2_2") (pintype "passive"))
      (node (ref "IC1") (pin "4") (pinfunction "-V_4") (pintype "passive"))
      (node (ref "L2") (pin "2") (pinfunction "2_2") (pintype "passive"))
      (node (ref "P2") (pin "1") (pinfunction "1_1") (pintype "passive"))
      (node (ref "P3") (pin "1") (pinfunction "1_1") (pintype "passive"))
      (node (ref "P4") (pin "2") (pinfunction "2_2") (pintype "passive"))
      (node (ref "Q8") (pin "2") (pinfunction "S_2") (pintype "passive"))
      (node (ref "Q9") (pin "2") (pinfunction "S_2") (pintype "passive"))
      (node (ref "R11") (pin "1") (pinfunction "1_1") (pintype "passive"))
      (node (ref "R4") (pin "1") (pinfunction "1_1") (pintype "passive"))
      (node (ref "R93") (pin "2") (pinfunction "2_2") (pintype "passive"))
      (node (ref "R99") (pin "1") (pinfunction "1_1") (pintype "passive"))
      (node (ref "U13") (pin "4") (pinfunction "VSS_4") (pintype "passive"))
      (node (ref "U20") (pin "1") (pinfunction "GND_1") (pintype "power_in"))
      (node (ref "U20") (pin "41") (pinfunction "EPAD_41") (pintype "power_in"))
      (node (ref "U4") (pin "23") (pinfunction "VSS_1_23") (pintype "passive"))
      (node (ref "U4") (pin "35") (pinfunction "VSS_2_35") (pintype "passive"))
      (node (ref "U4") (pin "47") (pinfunction "VSS_3_47") (pintype "passive"))
      (node (ref "U4") (pin "8") (pinfunction "VSS_A_8") (pintype "passive"))
      (node (ref "U5") (pin "1") (pinfunction "RES1_1") (pintype "passive"))
      (node (ref "U5") (pin "4") (pinfunction "AVSS_4") (pintype "passive"))
      (node (ref "U5") (pin "8") (pinfunction "DVSS_8") (pintype "passive"))
      (node (ref "Y1") (pin "2") (pinfunction "GND_2") (pintype "passive"))
      (node (ref "Y1") (pin "4") (pinfunction "GND_4") (pintype "passive"))
      (node (ref "Y3") (pin "2") (pinfunction "6_2") (pintype "passive"))
      (node (ref "Y3") (pin "4") (pinfunction "4_4") (pintype "passive"))
    )
    (net (code "58") (name "Net-(C78-Pad2)") (class "Default")
      (node (ref "C78") (pin "2") (pinfunction "2_2") (pintype "passive"))
      (node (ref "C80") (pin "1") (pinfunction "1_1") (pintype "passive"))
      (node (ref "L2") (pin "1") (pinfunction "1_1") (pintype "passive"))
    )
    (net (code "59") (name "Net-(C79-Pad2)") (class "Default")
      (node (ref "C79") (pin "2") (pinfunction "2_2") (pintype "passive"))
      (node (ref "C81") (pin "1") (pinfunction "1_1") (pintype "passive"))
      (node (ref "L5") (pin "1") (pinfunction "1_1") (pintype "passive"))
    )
    (net (code "60") (name "Net-(C80-Pad2)") (class "Default")
      (node (ref "C80") (pin "2") (pinfunction "2_2") (pintype "passive"))
      (node (ref "L3") (pin "1") (pinfunction "1_1") (pintype "passive"))
      (node (ref "L5") (pin "2") (pinfunction "2_2") (pintype "passive"))
    )
    (net (code "61") (name "Net-(C82-Pad1)") (class "Default")
      (node (ref "C82") (pin "1") (pinfunction "1_1") (pintype "passive"))
      (node (ref "L3") (pin "2") (pinfunction "2_2") (pintype "passive"))
      (node (ref "L4") (pin "1") (pinfunction "1_1") (pintype "passive"))
    )
    (net (code "62") (name "Net-(D1-A)") (class "Default")
      (node (ref "D1") (pin "1") (pinfunction "A_1") (pintype "passive"))
      (node (ref "R24") (pin "1") (pinfunction "1_1") (pintype "passive"))
    )
    (net (code "63") (name "Net-(D2-A)") (class "Default")
      (node (ref "D2") (pin "1") (pinfunction "A_1") (pintype "passive"))
      (node (ref "R9") (pin "1") (pinfunction "1_1") (pintype "passive"))
    )
    (net (code "64") (name "Net-(E1-A)") (class "Default")
      (node (ref "E1") (pin "1") (pinfunction "A_1") (pintype "passive"))
      (node (ref "L4") (pin "2") (pinfunction "2_2") (pintype "passive"))
    )
    (net (code "65") (name "Net-(FB1-Pad2)") (class "Default")
      (node (ref "FB1") (pin "2") (pinfunction "2_2") (pintype "passive"))
      (node (ref "R1") (pin "1") (pinfunction "1_1") (pintype "passive"))
    )
    (net (code "66") (name "Net-(IC1A-IN-)") (class "Default")
      (node (ref "IC1") (pin "2") (pinfunction "IN-_2") (pintype "input"))
      (node (ref "R27") (pin "2") (pinfunction "2_2") (pintype "passive"))
      (node (ref "R36") (pin "2") (pinfunction "2_2") (pintype "passive"))
    )
    (net (code "67") (name "Net-(IC1B-IN-)") (class "Default")
      (node (ref "IC1") (pin "6") (pinfunction "IN-_6") (pintype "input"))
      (node (ref "R38") (pin "1") (pinfunction "1_1") (pintype "passive"))
      (node (ref "R39") (pin "2") (pinfunction "2_2") (pintype "passive"))
      (node (ref "R8") (pin "1") (pinfunction "1_1") (pintype "passive"))
    )
    (net (code "68") (name "Net-(Q1-B)") (class "Default")
      (node (ref "Q1") (pin "1") (pinfunction "B_1") (pintype "passive"))
      (node (ref "Q2") (pin "1") (pinfunction "B_1") (pintype "passive"))
      (node (ref "R23") (pin "1") (pinfunction "1_1") (pintype "passive"))
    )
    (net (code "69") (name "Net-(Q9-G)") (class "Default")
      (node (ref "C86") (pin "2") (pinfunction "2_2") (pintype "passive"))
      (node (ref "Q9") (pin "1") (pinfunction "G_1") (pintype "passive"))
      (node (ref "R82") (pin "2") (pinfunction "2_2") (pintype "passive"))
      (node (ref "U3") (pin "1") (pinfunction "1B_1") (pintype "input"))
    )
    (net (code "70") (name "Net-(U3-2B)") (class "Default")
      (node (ref "R83") (pin "1") (pinfunction "1_1") (pintype "passive"))
      (node (ref "U3") (pin "2") (pinfunction "2B_2") (pintype "input"))
    )
    (net (code "71") (name "Net-(U3-GND)") (class "Default")
      (node (ref "F3") (pin "1") (pinfunction "1_1") (pintype "passive"))
      (node (ref "U3") (pin "8") (pinfunction "GND_8") (pintype "power_in"))
    )
    (net (code "72") (name "Net-(U4-BOOT_0)") (class "Default")
      (node (ref "R11") (pin "2") (pinfunction "2_2") (pintype "passive"))
      (node (ref "U4") (pin "44") (pinfunction "BOOT_0_44") (pintype "passive"))
    )
    (net (code "73") (name "Net-(U4-~{NRST})") (class "Default")
      (node (ref "C6") (pin "1") (pinfunction "1_1") (pintype "passive"))
      (node (ref "U4") (pin "7") (pinfunction "~{NRST}_7") (pintype "passive"))
    )
    (net (code "74") (name "Net-(U20-DCOUPL)") (class "Default")
      (node (ref "C83") (pin "1") (pinfunction "1_1") (pintype "passive"))
      (node (ref "U20") (pin "40") (pinfunction "DCOUPL_40") (pintype "power_in"))
    )
    (net (code "75") (name "Net-(U20-P2_3_{slash}_XOSC32K_Q2)") (class "Default")
      (node (ref "C88") (pin "2") (pinfunction "2_2") (pintype "passive"))
      (node (ref "U20") (pin "33") (pinfunction "P2_3_/_XOSC32K_Q2_33") (pintype "passive"))
      (node (ref "Y4") (pin "1") (pinfunction "OSC1_1") (pintype "passive"))
    )
    (net (code "76") (name "Net-(U20-P2_4_{slash}_XOSC32K_Q1)") (class "Default")
      (node (ref "C89") (pin "2") (pinfunction "2_2") (pintype "passive"))
      (node (ref "U20") (pin "32") (pinfunction "P2_4_/_XOSC32K_Q1_32") (pintype "passive"))
      (node (ref "Y4") (pin "2") (pinfunction "OSC2_2") (pintype "passive"))
    )
    (net (code "77") (name "Net-(U20-RF_N)") (class "Default")
      (node (ref "C79") (pin "1") (pinfunction "1_1") (pintype "passive"))
      (node (ref "U20") (pin "26") (pinfunction "RF_N_26") (pintype "bidirectional"))
    )
    (net (code "78") (name "Net-(U20-RF_P)") (class "Default")
      (node (ref "C78") (pin "1") (pinfunction "1_1") (pintype "passive"))
      (node (ref "U20") (pin "25") (pinfunction "RF_P_25") (pintype "bidirectional"))
    )
    (net (code "79") (name "Net-(U20-R_BIAS)") (class "Default")
      (node (ref "R99") (pin "2") (pinfunction "2_2") (pintype "passive"))
      (node (ref "U20") (pin "30") (pinfunction "R_BIAS_30") (pintype "bidirectional"))
    )
    (net (code "80") (name "Net-(U20-XOSC_Q1)") (class "Default")
      (node (ref "C87") (pin "2") (pinfunction "2_2") (pintype "passive"))
      (node (ref "U20") (pin "22") (pinfunction "XOSC_Q1_22") (pintype "bidirectional"))
      (node (ref "Y3") (pin "1") (pintype "passive"))
    )
    (net (code "81") (name "Net-(U20-XOSC_Q2)") (class "Default")
      (node (ref "C84") (pin "2") (pinfunction "2_2") (pintype "passive"))
      (node (ref "U20") (pin "23") (pinfunction "XOSC_Q2_23") (pintype "bidirectional"))
      (node (ref "Y3") (pin "3") (pinfunction "1_3") (pintype "passive"))
    )
    (net (code "82") (name "VDD1") (class "Default")
      (node (ref "C91") (pin "2") (pinfunction "2_2") (pintype "passive"))
      (node (ref "FB2") (pin "1") (pinfunction "1_1") (pintype "passive"))
      (node (ref "U20") (pin "39") (pinfunction "DVDD1_39") (pintype "power_in"))
    )
    (net (code "83") (name "VDD_RF") (class "Default")
      (node (ref "C71") (pin "1") (pinfunction "1_1") (pintype "passive"))
      (node (ref "C72") (pin "1") (pinfunction "1_1") (pintype "passive"))
      (node (ref "C73") (pin "1") (pinfunction "1_1") (pintype "passive"))
      (node (ref "C74") (pin "1") (pinfunction "1_1") (pintype "passive"))
      (node (ref "C76") (pin "1") (pinfunction "1_1") (pintype "passive"))
      (node (ref "C77") (pin "1") (pinfunction "1_1") (pintype "passive"))
      (node (ref "FB1") (pin "1") (pinfunction "1_1") (pintype "passive"))
      (node (ref "U20") (pin "10") (pinfunction "DVDD2_10") (pintype "power_in"))
      (node (ref "U20") (pin "21") (pinfunction "AVDD5_21") (pintype "power_in"))
      (node (ref "U20") (pin "24") (pinfunction "AVDD3_24") (pintype "power_in"))
      (node (ref "U20") (pin "27") (pinfunction "AVDD2_27") (pintype "power_in"))
      (node (ref "U20") (pin "28") (pinfunction "AVDD1_28") (pintype "power_in"))
      (node (ref "U20") (pin "29") (pinfunction "AVDD4_29") (pintype "power_in"))
      (node (ref "U20") (pin "31") (pinfunction "AVDD6_31") (pintype "power_in"))
    )
    (net (code "84") (name "VIN") (class "Default")
      (node (ref "P4") (pin "1") (pinfunction "1_1") (pintype "passive"))
      (node (ref "R67") (pin "1") (pinfunction "1_1") (pintype "passive"))
      (node (ref "U3") (pin "9") (pinfunction "COM_9") (pintype "passive"))
    )
    (net (code "85") (name "unconnected-(U4-PA2{slash}USART2_TX{slash}AIN2{slash}TIM2_CH3{slash}TIM15_CH1-Pad12)") (class "Default")
      (node (ref "U4") (pin "12") (pinfunction "PA2/USART2_TX/AIN2/TIM2_CH3/TIM15_CH1_12") (pintype "passive"))
    )
    (net (code "86") (name "unconnected-(U5-N{slash}C-Pad2)") (class "Default")
      (node (ref "U5") (pin "2") (pinfunction "N/C_2") (pintype "passive+no_connect"))
    )
    (net (code "87") (name "unconnected-(U5-RES-Pad10)") (class "Default")
      (node (ref "U5") (pin "10") (pinfunction "RES_10") (pintype "passive+no_connect"))
    )
    (net (code "88") (name "unconnected-(U20-NC-Pad4)") (class "Default")
      (node (ref "U20") (pin "4") (pinfunction "NC_4") (pintype "power_in"))
    )
    (net (code "89") (name "unconnected-(U20-P0_0-Pad19)") (class "Default")
      (node (ref "U20") (pin "19") (pinfunction "P0_0_19") (pintype "bidirectional"))
    )
    (net (code "90") (name "unconnected-(U20-P0_3-Pad16)") (class "Default")
      (node (ref "U20") (pin "16") (pinfunction "P0_3_16") (pintype "bidirectional"))
    )
    (net (code "91") (name "unconnected-(U20-P0_4-Pad15)") (class "Default")
      (node (ref "U20") (pin "15") (pinfunction "P0_4_15") (pintype "bidirectional"))
    )
    (net (code "92") (name "unconnected-(U20-P0_5-Pad14)") (class "Default")
      (node (ref "U20") (pin "14") (pinfunction "P0_5_14") (pintype "bidirectional"))
    )
    (net (code "93") (name "unconnected-(U20-P0_6-Pad13)") (class "Default")
      (node (ref "U20") (pin "13") (pinfunction "P0_6_13") (pintype "bidirectional"))
    )
    (net (code "94") (name "unconnected-(U20-P0_7-Pad12)") (class "Default")
      (node (ref "U20") (pin "12") (pinfunction "P0_7_12") (pintype "bidirectional"))
    )
    (net (code "95") (name "unconnected-(U20-P1_0-Pad11)") (class "Default")
      (node (ref "U20") (pin "11") (pinfunction "P1_0_11") (pintype "bidirectional"))
    )
    (net (code "96") (name "unconnected-(U20-P1_1-Pad9)") (class "Default")
      (node (ref "U20") (pin "9") (pinfunction "P1_1_9") (pintype "bidirectional"))
    )
    (net (code "97") (name "unconnected-(U20-P1_2-Pad8)") (class "Default")
      (node (ref "U20") (pin "8") (pinfunction "P1_2_8") (pintype "bidirectional"))
    )
    (net (code "98") (name "unconnected-(U20-P1_3-Pad7)") (class "Default")
      (node (ref "U20") (pin "7") (pinfunction "P1_3_7") (pintype "bidirectional"))
    )
    (net (code "99") (name "unconnected-(U20-P1_4-Pad6)") (class "Default")
      (node (ref "U20") (pin "6") (pinfunction "P1_4_6") (pintype "bidirectional"))
    )
    (net (code "100") (name "unconnected-(U20-P1_5-Pad5)") (class "Default")
      (node (ref "U20") (pin "5") (pinfunction "P1_5_5") (pintype "bidirectional"))
    )
    (net (code "101") (name "unconnected-(U20-P1_6-Pad38)") (class "Default")
      (node (ref "U20") (pin "38") (pinfunction "P1_6_38") (pintype "bidirectional"))
    )
    (net (code "102") (name "unconnected-(U20-P1_7-Pad37)") (class "Default")
      (node (ref "U20") (pin "37") (pinfunction "P1_7_37") (pintype "bidirectional"))
    )
    (net (code "103") (name "unconnected-(U20-P2_0-Pad36)") (class "Default")
      (node (ref "U20") (pin "36") (pinfunction "P2_0_36") (pintype "bidirectional"))
    )
  )
)
